# QCopterFC_SD_Sch.net
KiCad netlist of a schematic drawn in Altium Designer
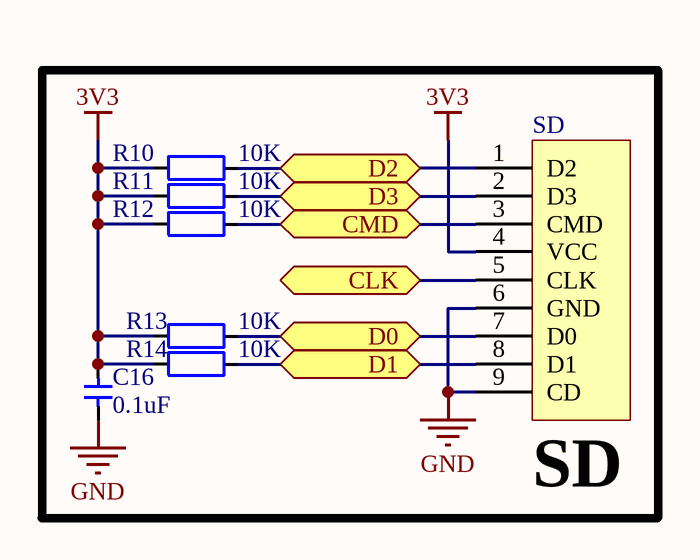
[diagram p0: QCopterFC_SD_Sch.SchDoc]

(export (version "E")
  (design (tool "Eeschema 10.0.6"))
  (components
    (comp (ref "C16")
      (value "0.1uF")
      (footprint "PCB_Passive:CAP_0603")
      (description "Capacitor")
      (fields (field (name "Comment") "Cap_0603"))
      (libsource (lib "SCH_Passive") (part "Cap_0603"))
    )
    (comp (ref "R10")
      (value "10K")
      (footprint "PCB_Passive:RES_0603")
      (description "Resistor")
      (fields (field (name "Comment") "Res_0603"))
      (libsource (lib "SCH_Passive") (part "Res_0603"))
    )
    (comp (ref "R11")
      (value "10K")
      (footprint "PCB_Passive:RES_0603")
      (description "Resistor")
      (fields (field (name "Comment") "Res_0603"))
      (libsource (lib "SCH_Passive") (part "Res_0603"))
    )
    (comp (ref "R12")
      (value "10K")
      (footprint "PCB_Passive:RES_0603")
      (description "Resistor")
      (fields (field (name "Comment") "Res_0603"))
      (libsource (lib "SCH_Passive") (part "Res_0603"))
    )
    (comp (ref "R13")
      (value "10K")
      (footprint "PCB_Passive:RES_0603")
      (description "Resistor")
      (fields (field (name "Comment") "Res_0603"))
      (libsource (lib "SCH_Passive") (part "Res_0603"))
    )
    (comp (ref "R14")
      (value "10K")
      (footprint "PCB_Passive:RES_0603")
      (description "Resistor")
      (fields (field (name "Comment") "Res_0603"))
      (libsource (lib "SCH_Passive") (part "Res_0603"))
    )
    (comp (ref "SD")
      (value "SD_Card_TF")
      (footprint "PCB_SDCard:SD_Card_TF")
      (description "SD")
      (libsource (lib "SCH_SDCard") (part "SD_Card_TF"))
    )
  )
  (nets
    (net (code "1") (name "/CLK") (class "Default")
      (node (ref "SD") (pin "5") (pinfunction "CLK_5") (pintype "passive"))
    )
    (net (code "2") (name "/CMD") (class "Default")
      (node (ref "R12") (pin "1") (pinfunction "1_1") (pintype "passive"))
      (node (ref "SD") (pin "3") (pinfunction "CMD_3") (pintype "passive"))
    )
    (net (code "3") (name "/D0") (class "Default")
      (node (ref "R13") (pin "1") (pinfunction "1_1") (pintype "passive"))
      (node (ref "SD") (pin "7") (pinfunction "D0_7") (pintype "passive"))
    )
    (net (code "4") (name "/D1") (class "Default")
      (node (ref "R14") (pin "1") (pinfunction "1_1") (pintype "passive"))
      (node (ref "SD") (pin "8") (pinfunction "D1_8") (pintype "passive"))
    )
    (net (code "5") (name "/D2") (class "Default")
      (node (ref "R10") (pin "1") (pinfunction "1_1") (pintype "passive"))
      (node (ref "SD") (pin "1") (pinfunction "D2_1") (pintype "passive"))
    )
    (net (code "6") (name "/D3") (class "Default")
      (node (ref "R11") (pin "1") (pinfunction "1_1") (pintype "passive"))
      (node (ref "SD") (pin "2") (pinfunction "D3_2") (pintype "passive"))
    )
    (net (code "8") (name "3V3") (class "Default")
      (node (ref "C16") (pin "2") (pinfunction "2_2") (pintype "passive"))
      (node (ref "R10") (pin "2") (pinfunction "2_2") (pintype "passive"))
      (node (ref "R11") (pin "2") (pinfunction "2_2") (pintype "passive"))
      (node (ref "R12") (pin "2") (pinfunction "2_2") (pintype "passive"))
      (node (ref "R13") (pin "2") (pinfunction "2_2") (pintype "passive"))
      (node (ref "R14") (pin "2") (pinfunction "2_2") (pintype "passive"))
      (node (ref "SD") (pin "4") (pinfunction "VCC_4") (pintype "passive"))
    )
    (net (code "9") (name "GND") (class "Default")
      (node (ref "C16") (pin "1") (pinfunction "1_1") (pintype "passive"))
      (node (ref "SD") (pin "6") (pinfunction "GND_6") (pintype "passive"))
      (node (ref "SD") (pin "9") (pinfunction "CD_9") (pintype "passive"))
    )
  )
)
